# BABYBEAR.net
KiCad netlist of a schematic drawn in EAGLE
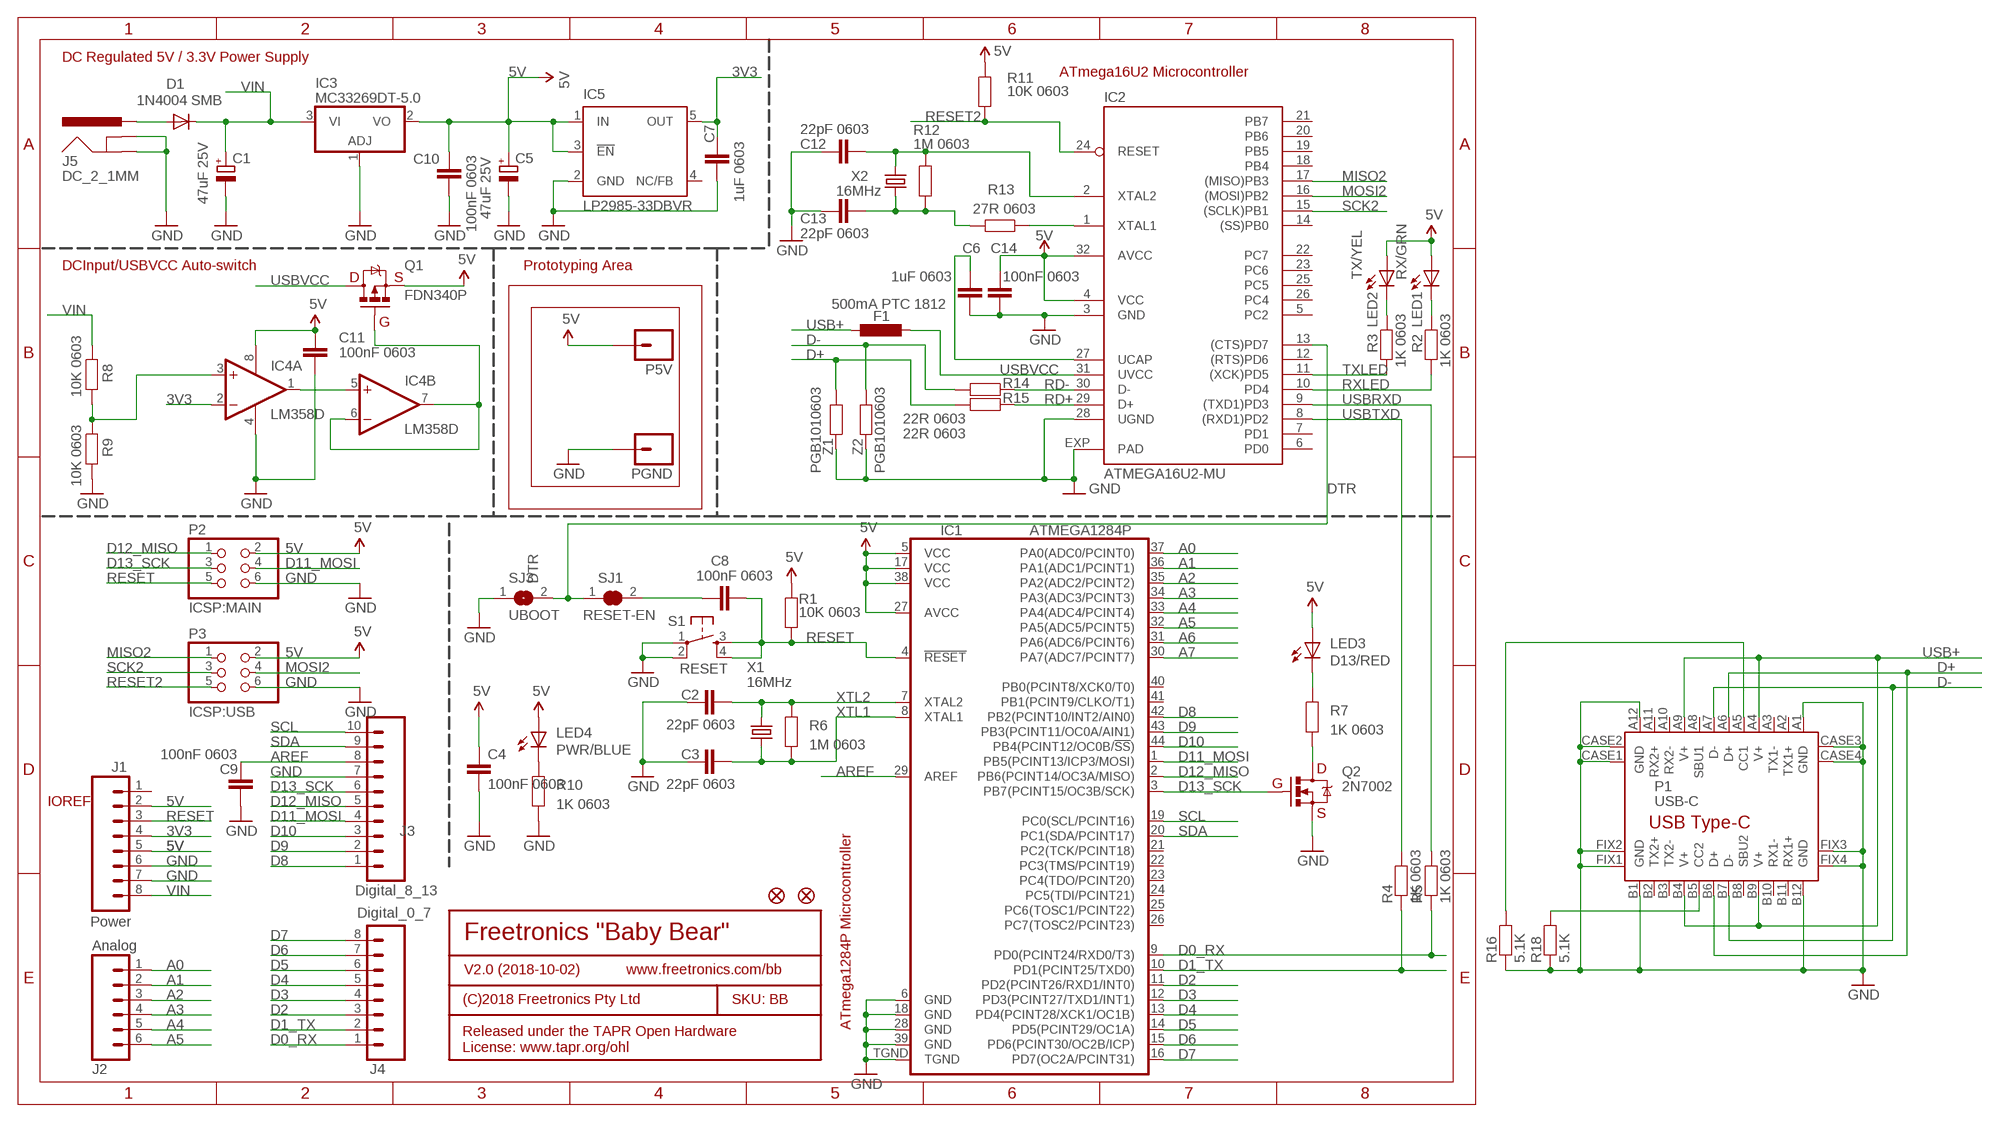
[diagram p0: schematic, sheet 1]

(export (version "E")
  (design (tool "Eeschema 10.0.6"))
  (components
    (comp (ref "C1")
      (value "47uF 25V")
      (footprint "eagle-import:PANASONIC_D")
      (libsource (lib "eagle-import") (part "CPOL-EUD"))
    )
    (comp (ref "C2")
      (value "22pF 0603")
      (footprint "eagle-import:0603")
      (libsource (lib "eagle-import") (part "CAP0603"))
    )
    (comp (ref "C3")
      (value "22pF 0603")
      (footprint "eagle-import:0603")
      (libsource (lib "eagle-import") (part "CAP0603"))
    )
    (comp (ref "C4")
      (value "100nF 0603")
      (footprint "eagle-import:0603")
      (libsource (lib "eagle-import") (part "CAP0603"))
    )
    (comp (ref "C5")
      (value "47uF 25V")
      (footprint "eagle-import:PANASONIC_D")
      (libsource (lib "eagle-import") (part "CPOL-EUD"))
    )
    (comp (ref "C6")
      (value "1uF 0603")
      (footprint "eagle-import:0603")
      (libsource (lib "eagle-import") (part "CAP0603"))
    )
    (comp (ref "C7")
      (value "1uF 0603")
      (footprint "eagle-import:0603")
      (libsource (lib "eagle-import") (part "CAP0603"))
    )
    (comp (ref "C8")
      (value "100nF 0603")
      (footprint "eagle-import:0603")
      (libsource (lib "eagle-import") (part "CAP0603"))
    )
    (comp (ref "C9")
      (value "100nF 0603")
      (footprint "eagle-import:0603")
      (libsource (lib "eagle-import") (part "CAP0603"))
    )
    (comp (ref "C10")
      (value "100nF 0603")
      (footprint "eagle-import:0603")
      (libsource (lib "eagle-import") (part "CAP0603"))
    )
    (comp (ref "C11")
      (value "100nF 0603")
      (footprint "eagle-import:0603")
      (libsource (lib "eagle-import") (part "CAP0603"))
    )
    (comp (ref "C12")
      (value "22pF 0603")
      (footprint "eagle-import:0603")
      (libsource (lib "eagle-import") (part "CAP0603"))
    )
    (comp (ref "C13")
      (value "22pF 0603")
      (footprint "eagle-import:0603")
      (libsource (lib "eagle-import") (part "CAP0603"))
    )
    (comp (ref "C14")
      (value "100nF 0603")
      (footprint "eagle-import:0603")
      (libsource (lib "eagle-import") (part "CAP0603"))
    )
    (comp (ref "D1")
      (value "1N4004 SMB")
      (footprint "eagle-import:SMB-DIODE")
      (libsource (lib "eagle-import") (part "DIODESMB"))
    )
    (comp (ref "F1")
      (value "500mA PTC 1812")
      (footprint "eagle-import:L1812")
      (libsource (lib "eagle-import") (part "L-EUL1812"))
    )
    (comp (ref "IC1")
      (value "ATMEGA1284P")
      (footprint "eagle-import:QFN-44M1")
      (libsource (lib "eagle-import") (part "ATMEGA1284P"))
    )
    (comp (ref "IC2")
      (value "ATMEGA16U2-MU")
      (footprint "eagle-import:ATMEL_QFN32")
      (libsource (lib "eagle-import") (part "ATMEL_ATMEGA8U2-MUQFN"))
    )
    (comp (ref "IC3")
      (value "MC33269DT-5.0")
      (footprint "eagle-import:DPACK")
      (libsource (lib "eagle-import") (part "MC33269?D-5.0"))
    )
    (comp (ref "IC4")
      (value "LM358D")
      (footprint "eagle-import:SO08")
      (libsource (lib "eagle-import") (part "LM358D"))
    )
    (comp (ref "IC5")
      (value "LP2985-33DBVR")
      (footprint "eagle-import:TEXAS_SOT23-DBV")
      (libsource (lib "eagle-import") (part "TEXAS_TPS77033"))
    )
    (comp (ref "J1")
      (value "Power")
      (footprint "eagle-import:1X08")
      (libsource (lib "eagle-import") (part "M08"))
    )
    (comp (ref "J2")
      (value "Analog")
      (footprint "eagle-import:1X06")
      (libsource (lib "eagle-import") (part "M06SIP"))
    )
    (comp (ref "J3")
      (value "Digital_8_13")
      (footprint "eagle-import:1X10")
      (libsource (lib "eagle-import") (part "M100.1"))
    )
    (comp (ref "J4")
      (value "Digital_0_7")
      (footprint "eagle-import:1X08")
      (libsource (lib "eagle-import") (part "M08"))
    )
    (comp (ref "J5")
      (value "DC_2_1MM")
      (footprint "eagle-import:POWER_JACK_PTH_SLOTS")
      (libsource (lib "eagle-import") (part "POWER_JACKPTH_SLOTS"))
    )
    (comp (ref "LED1")
      (value "RX/GRN")
      (footprint "eagle-import:LED-0603")
      (libsource (lib "eagle-import") (part "LED0603"))
    )
    (comp (ref "LED2")
      (value "TX/YEL")
      (footprint "eagle-import:LED-0603")
      (libsource (lib "eagle-import") (part "LED0603"))
    )
    (comp (ref "LED3")
      (value "D13/RED")
      (footprint "eagle-import:LED-0603")
      (libsource (lib "eagle-import") (part "LED0603"))
    )
    (comp (ref "LED4")
      (value "PWR/BLUE")
      (footprint "eagle-import:LED-0603")
      (libsource (lib "eagle-import") (part "LED0603"))
    )
    (comp (ref "P1")
      (value "USB-C")
      (footprint "eagle-import:USB-C-U52A")
      (libsource (lib "eagle-import") (part "USB-C"))
    )
    (comp (ref "P2")
      (value "ICSP:MAIN")
      (footprint "eagle-import:2X03")
      (libsource (lib "eagle-import") (part "PINHD-2X3"))
    )
    (comp (ref "P3")
      (value "ICSP:USB")
      (footprint "eagle-import:2X03")
      (libsource (lib "eagle-import") (part "PINHD-2X3"))
    )
    (comp (ref "P5V")
      (value "M01SMD")
      (footprint "eagle-import:LUXEON-PAD")
      (libsource (lib "eagle-import") (part "M01SMD"))
    )
    (comp (ref "PGND")
      (value "M01SMD")
      (footprint "eagle-import:LUXEON-PAD")
      (libsource (lib "eagle-import") (part "M01SMD"))
    )
    (comp (ref "Q1")
      (value "FDN340P")
      (footprint "eagle-import:SOT23")
      (libsource (lib "eagle-import") (part "MOSFET-PCHANNEL"))
    )
    (comp (ref "Q2")
      (value "2N7002")
      (footprint "eagle-import:SOT23-3")
      (libsource (lib "eagle-import") (part "MOSFET-NCHANNELSMD"))
    )
    (comp (ref "R1")
      (value "10K 0603")
      (footprint "eagle-import:0603")
      (libsource (lib "eagle-import") (part "RESISTOR0603"))
    )
    (comp (ref "R2")
      (value "1K 0603")
      (footprint "eagle-import:0603")
      (libsource (lib "eagle-import") (part "RESISTOR0603"))
    )
    (comp (ref "R3")
      (value "1K 0603")
      (footprint "eagle-import:0603")
      (libsource (lib "eagle-import") (part "RESISTOR0603"))
    )
    (comp (ref "R4")
      (value "1K 0603")
      (footprint "eagle-import:0603")
      (libsource (lib "eagle-import") (part "RESISTOR0603"))
    )
    (comp (ref "R5")
      (value "1K 0603")
      (footprint "eagle-import:0603")
      (libsource (lib "eagle-import") (part "RESISTOR0603"))
    )
    (comp (ref "R6")
      (value "1M 0603")
      (footprint "eagle-import:0603")
      (libsource (lib "eagle-import") (part "RESISTOR0603"))
    )
    (comp (ref "R7")
      (value "1K 0603")
      (footprint "eagle-import:0603")
      (libsource (lib "eagle-import") (part "RESISTOR0603"))
    )
    (comp (ref "R8")
      (value "10K 0603")
      (footprint "eagle-import:0603")
      (libsource (lib "eagle-import") (part "RESISTOR0603"))
    )
    (comp (ref "R9")
      (value "10K 0603")
      (footprint "eagle-import:0603")
      (libsource (lib "eagle-import") (part "RESISTOR0603"))
    )
    (comp (ref "R10")
      (value "1K 0603")
      (footprint "eagle-import:0603")
      (libsource (lib "eagle-import") (part "RESISTOR0603"))
    )
    (comp (ref "R11")
      (value "10K 0603")
      (footprint "eagle-import:0603")
      (libsource (lib "eagle-import") (part "RESISTOR0603"))
    )
    (comp (ref "R12")
      (value "1M 0603")
      (footprint "eagle-import:0603")
      (libsource (lib "eagle-import") (part "RESISTOR0603"))
    )
    (comp (ref "R13")
      (value "27R 0603")
      (footprint "eagle-import:0603")
      (libsource (lib "eagle-import") (part "RESISTOR0603"))
    )
    (comp (ref "R14")
      (value "22R 0603")
      (footprint "eagle-import:0603")
      (libsource (lib "eagle-import") (part "RESISTOR0603"))
    )
    (comp (ref "R15")
      (value "22R 0603")
      (footprint "eagle-import:0603")
      (libsource (lib "eagle-import") (part "RESISTOR0603"))
    )
    (comp (ref "R16")
      (value "5.1K")
      (footprint "eagle-import:0603")
      (libsource (lib "eagle-import") (part "freetronics-original_RESISTOR0603"))
    )
    (comp (ref "R18")
      (value "5.1K")
      (footprint "eagle-import:0603")
      (libsource (lib "eagle-import") (part "freetronics-original_RESISTOR0603"))
    )
    (comp (ref "S1")
      (value "RESET")
      (footprint "eagle-import:TACTILE_SWITCH_SMD")
      (libsource (lib "eagle-import") (part "TAC_SWITCHSMD"))
    )
    (comp (ref "SJ1")
      (value "RESET-EN")
      (footprint "eagle-import:SJC")
      (libsource (lib "eagle-import") (part "SJCN"))
    )
    (comp (ref "SJ3")
      (value "UBOOT")
      (footprint "eagle-import:SJ")
      (libsource (lib "eagle-import") (part "SJ"))
    )
    (comp (ref "U$5")
      (value "FIDUCIAL1X2.5")
      (footprint "eagle-import:FIDUCIAL-1X2.5")
      (libsource (lib "eagle-import") (part "FIDUCIAL1X2.5"))
    )
    (comp (ref "U$14")
      (value "FIDUCIAL1X2.5")
      (footprint "eagle-import:FIDUCIAL-1X2.5")
      (libsource (lib "eagle-import") (part "FIDUCIAL1X2.5"))
    )
    (comp (ref "X1")
      (value "16MHz")
      (footprint "eagle-import:HC49U-V")
      (libsource (lib "eagle-import") (part "CRYSTALHC49UV"))
    )
    (comp (ref "X2")
      (value "16MHz")
      (footprint "eagle-import:HC49U-V")
      (libsource (lib "eagle-import") (part "CRYSTALHC49UV"))
    )
    (comp (ref "Z1")
      (value "PGB1010603")
      (footprint "eagle-import:0603")
      (libsource (lib "eagle-import") (part "RESISTOR0603"))
    )
    (comp (ref "Z2")
      (value "PGB1010603")
      (footprint "eagle-import:0603")
      (libsource (lib "eagle-import") (part "RESISTOR0603"))
    )
  )
  (nets
    (net (code "1") (name "/3V3") (class "Default")
      (node (ref "C7") (pin "2") (pinfunction "2_2") (pintype "passive"))
      (node (ref "IC4") (pin "2") (pinfunction "-IN_2") (pintype "input"))
      (node (ref "IC5") (pin "5") (pinfunction "OUT_5") (pintype "passive"))
      (node (ref "J1") (pin "4") (pinfunction "4_4") (pintype "passive"))
    )
    (net (code "2") (name "/A0") (class "Default")
      (node (ref "IC1") (pin "37") (pinfunction "PA0(ADC0/PCINT0)_37") (pintype "bidirectional"))
      (node (ref "J2") (pin "1") (pinfunction "1_1") (pintype "passive"))
    )
    (net (code "3") (name "/A1") (class "Default")
      (node (ref "IC1") (pin "36") (pinfunction "PA1(ADC1/PCINT1)_36") (pintype "bidirectional"))
      (node (ref "J2") (pin "2") (pinfunction "2_2") (pintype "passive"))
    )
    (net (code "4") (name "/A2") (class "Default")
      (node (ref "IC1") (pin "35") (pinfunction "PA2(ADC2/PCINT2)_35") (pintype "bidirectional"))
      (node (ref "J2") (pin "3") (pinfunction "3_3") (pintype "passive"))
    )
    (net (code "5") (name "/A3") (class "Default")
      (node (ref "IC1") (pin "34") (pinfunction "PA3(ADC3/PCINT3)_34") (pintype "bidirectional"))
      (node (ref "J2") (pin "4") (pinfunction "4_4") (pintype "passive"))
    )
    (net (code "6") (name "/A4") (class "Default")
      (node (ref "IC1") (pin "33") (pinfunction "PA4(ADC4/PCINT4)_33") (pintype "bidirectional"))
      (node (ref "J2") (pin "5") (pinfunction "5_5") (pintype "passive"))
    )
    (net (code "7") (name "/A5") (class "Default")
      (node (ref "IC1") (pin "32") (pinfunction "PA5(ADC5/PCINT5)_32") (pintype "bidirectional"))
      (node (ref "J2") (pin "6") (pinfunction "6_6") (pintype "passive"))
    )
    (net (code "8") (name "/A6") (class "Default")
      (node (ref "IC1") (pin "31") (pinfunction "PA6(ADC6/PCINT6)_31") (pintype "bidirectional"))
    )
    (net (code "9") (name "/A7") (class "Default")
      (node (ref "IC1") (pin "30") (pinfunction "PA7(ADC7/PCINT7)_30") (pintype "bidirectional"))
    )
    (net (code "10") (name "/AREF") (class "Default")
      (node (ref "C9") (pin "1") (pinfunction "1_1") (pintype "passive"))
      (node (ref "IC1") (pin "29") (pinfunction "AREF_29") (pintype "bidirectional"))
      (node (ref "J3") (pin "8") (pinfunction "8_8") (pintype "passive"))
    )
    (net (code "11") (name "/D+") (class "Default")
      (node (ref "P1") (pin "A6") (pinfunction "D+_A6") (pintype "bidirectional"))
      (node (ref "P1") (pin "B6") (pinfunction "D+_B6") (pintype "bidirectional"))
      (node (ref "R15") (pin "2") (pinfunction "2_2") (pintype "passive"))
      (node (ref "Z1") (pin "1") (pinfunction "1_1") (pintype "passive"))
    )
    (net (code "12") (name "/D-") (class "Default")
      (node (ref "P1") (pin "A7") (pinfunction "D-_A7") (pintype "bidirectional"))
      (node (ref "P1") (pin "B7") (pinfunction "D-_B7") (pintype "bidirectional"))
      (node (ref "R14") (pin "2") (pinfunction "2_2") (pintype "passive"))
      (node (ref "Z2") (pin "1") (pinfunction "1_1") (pintype "passive"))
    )
    (net (code "13") (name "/D0_RX") (class "Default")
      (node (ref "IC1") (pin "9") (pinfunction "PD0(PCINT24/RXD0/T3)_9") (pintype "bidirectional"))
      (node (ref "J4") (pin "1") (pinfunction "1_1") (pintype "passive"))
      (node (ref "R5") (pin "1") (pinfunction "1_1") (pintype "passive"))
    )
    (net (code "14") (name "/D1_TX") (class "Default")
      (node (ref "IC1") (pin "10") (pinfunction "PD1(PCINT25/TXD0)_10") (pintype "bidirectional"))
      (node (ref "J4") (pin "2") (pinfunction "2_2") (pintype "passive"))
      (node (ref "R4") (pin "1") (pinfunction "1_1") (pintype "passive"))
    )
    (net (code "15") (name "/D2") (class "Default")
      (node (ref "IC1") (pin "11") (pinfunction "PD2(PCINT26/RXD1/INT0)_11") (pintype "bidirectional"))
      (node (ref "J4") (pin "3") (pinfunction "3_3") (pintype "passive"))
    )
    (net (code "16") (name "/D3") (class "Default")
      (node (ref "IC1") (pin "12") (pinfunction "PD3(PCINT27/TXD1/INT1)_12") (pintype "bidirectional"))
      (node (ref "J4") (pin "4") (pinfunction "4_4") (pintype "passive"))
    )
    (net (code "17") (name "/D4") (class "Default")
      (node (ref "IC1") (pin "13") (pinfunction "PD4(PCINT28/XCK1/OC1B)_13") (pintype "bidirectional"))
      (node (ref "J4") (pin "5") (pinfunction "5_5") (pintype "passive"))
    )
    (net (code "18") (name "/D5") (class "Default")
      (node (ref "IC1") (pin "14") (pinfunction "PD5(PCINT29/OC1A)_14") (pintype "bidirectional"))
      (node (ref "J4") (pin "6") (pinfunction "6_6") (pintype "passive"))
    )
    (net (code "19") (name "/D6") (class "Default")
      (node (ref "IC1") (pin "15") (pinfunction "PD6(PCINT30/OC2B/ICP)_15") (pintype "bidirectional"))
      (node (ref "J4") (pin "7") (pinfunction "7_7") (pintype "passive"))
    )
    (net (code "20") (name "/D7") (class "Default")
      (node (ref "IC1") (pin "16") (pinfunction "PD7(OC2A/PCINT31)_16") (pintype "bidirectional"))
      (node (ref "J4") (pin "8") (pinfunction "8_8") (pintype "passive"))
    )
    (net (code "21") (name "/D8") (class "Default")
      (node (ref "IC1") (pin "42") (pinfunction "PB2(PCINT10/INT2/AIN0)_42") (pintype "bidirectional"))
      (node (ref "J3") (pin "1") (pinfunction "1_1") (pintype "passive"))
    )
    (net (code "22") (name "/D9") (class "Default")
      (node (ref "IC1") (pin "43") (pinfunction "PB3(PCINT11/OC0A/AIN1)_43") (pintype "bidirectional"))
      (node (ref "J3") (pin "2") (pinfunction "2_2") (pintype "passive"))
    )
    (net (code "23") (name "/D10") (class "Default")
      (node (ref "IC1") (pin "44") (pinfunction "PB4(PCINT12/OC0B/~{SS})_44") (pintype "bidirectional"))
      (node (ref "J3") (pin "3") (pinfunction "3_3") (pintype "passive"))
    )
    (net (code "24") (name "/D11_MOSI") (class "Default")
      (node (ref "IC1") (pin "1") (pinfunction "PB5(PCINT13/ICP3/MOSI)_1") (pintype "bidirectional"))
      (node (ref "J3") (pin "4") (pinfunction "4_4") (pintype "passive"))
      (node (ref "P2") (pin "4") (pinfunction "4_4") (pintype "passive"))
    )
    (net (code "25") (name "/D12_MISO") (class "Default")
      (node (ref "IC1") (pin "2") (pinfunction "PB6(PCINT14/OC3A/MISO)_2") (pintype "bidirectional"))
      (node (ref "J3") (pin "5") (pinfunction "5_5") (pintype "passive"))
      (node (ref "P2") (pin "1") (pinfunction "1_1") (pintype "passive"))
    )
    (net (code "26") (name "/D13_SCK") (class "Default")
      (node (ref "IC1") (pin "3") (pinfunction "PB7(PCINT15/OC3B/SCK)_3") (pintype "bidirectional"))
      (node (ref "J3") (pin "6") (pinfunction "6_6") (pintype "passive"))
      (node (ref "P2") (pin "3") (pinfunction "3_3") (pintype "passive"))
      (node (ref "Q2") (pin "1") (pinfunction "G_1") (pintype "passive"))
    )
    (net (code "27") (name "/DTR") (class "Default")
      (node (ref "IC2") (pin "13") (pinfunction "(CTS)PD7_13") (pintype "bidirectional"))
      (node (ref "SJ1") (pin "1") (pinfunction "1_1") (pintype "passive"))
      (node (ref "SJ3") (pin "2") (pinfunction "2_2") (pintype "passive"))
    )
    (net (code "28") (name "/MISO2") (class "Default")
      (node (ref "IC2") (pin "17") (pinfunction "(MISO)PB3_17") (pintype "bidirectional"))
      (node (ref "P3") (pin "1") (pinfunction "1_1") (pintype "passive"))
    )
    (net (code "29") (name "/MOSI2") (class "Default")
      (node (ref "IC2") (pin "16") (pinfunction "(MOSI)PB2_16") (pintype "bidirectional"))
      (node (ref "P3") (pin "4") (pinfunction "4_4") (pintype "passive"))
    )
    (net (code "30") (name "/RD+") (class "Default")
      (node (ref "IC2") (pin "29") (pinfunction "D+_29") (pintype "bidirectional"))
      (node (ref "R15") (pin "1") (pinfunction "1_1") (pintype "passive"))
    )
    (net (code "31") (name "/RD-") (class "Default")
      (node (ref "IC2") (pin "30") (pinfunction "D-_30") (pintype "bidirectional"))
      (node (ref "R14") (pin "1") (pinfunction "1_1") (pintype "passive"))
    )
    (net (code "32") (name "/RESET") (class "Default")
      (node (ref "C8") (pin "2") (pinfunction "2_2") (pintype "passive"))
      (node (ref "IC1") (pin "4") (pinfunction "~{RESET}_4") (pintype "bidirectional"))
      (node (ref "J1") (pin "3") (pinfunction "3_3") (pintype "passive"))
      (node (ref "P2") (pin "5") (pinfunction "5_5") (pintype "passive"))
      (node (ref "R1") (pin "1") (pinfunction "1_1") (pintype "passive"))
      (node (ref "S1") (pin "3") (pinfunction "3_3") (pintype "passive"))
      (node (ref "S1") (pin "4") (pinfunction "4_4") (pintype "passive"))
    )
    (net (code "33") (name "/RESET2") (class "Default")
      (node (ref "IC2") (pin "24") (pinfunction "RESET_24") (pintype "input"))
      (node (ref "P3") (pin "5") (pinfunction "5_5") (pintype "passive"))
      (node (ref "R11") (pin "1") (pinfunction "1_1") (pintype "passive"))
    )
    (net (code "34") (name "/RXLED") (class "Default")
      (node (ref "IC2") (pin "10") (pinfunction "PD4_10") (pintype "bidirectional"))
      (node (ref "R2") (pin "1") (pinfunction "1_1") (pintype "passive"))
    )
    (net (code "35") (name "/SCK2") (class "Default")
      (node (ref "IC2") (pin "15") (pinfunction "(SCLK)PB1_15") (pintype "bidirectional"))
      (node (ref "P3") (pin "3") (pinfunction "3_3") (pintype "passive"))
    )
    (net (code "36") (name "/SCL") (class "Default")
      (node (ref "IC1") (pin "19") (pinfunction "PC0(SCL/PCINT16)_19") (pintype "bidirectional"))
      (node (ref "J3") (pin "10") (pinfunction "10_10") (pintype "passive"))
    )
    (net (code "37") (name "/SDA") (class "Default")
      (node (ref "IC1") (pin "20") (pinfunction "PC1(SDA/PCINT17)_20") (pintype "bidirectional"))
      (node (ref "J3") (pin "9") (pinfunction "9_9") (pintype "passive"))
    )
    (net (code "38") (name "/TXLED") (class "Default")
      (node (ref "IC2") (pin "11") (pinfunction "(XCK)PD5_11") (pintype "bidirectional"))
      (node (ref "R3") (pin "1") (pinfunction "1_1") (pintype "passive"))
    )
    (net (code "39") (name "/USB+") (class "Default")
      (node (ref "F1") (pin "1") (pinfunction "1_1") (pintype "passive"))
      (node (ref "P1") (pin "A4") (pinfunction "V+_A4") (pintype "power_in"))
      (node (ref "P1") (pin "A9") (pinfunction "V+_A9") (pintype "power_in"))
      (node (ref "P1") (pin "B4") (pinfunction "V+_B4") (pintype "power_in"))
      (node (ref "P1") (pin "B9") (pinfunction "V+_B9") (pintype "power_in"))
    )
    (net (code "40") (name "/USBRXD") (class "Default")
      (node (ref "IC2") (pin "9") (pinfunction "(TXD1)PD3_9") (pintype "bidirectional"))
      (node (ref "R5") (pin "2") (pinfunction "2_2") (pintype "passive"))
    )
    (net (code "41") (name "/USBTXD") (class "Default")
      (node (ref "IC2") (pin "8") (pinfunction "(RXD1)PD2_8") (pintype "bidirectional"))
      (node (ref "R4") (pin "2") (pinfunction "2_2") (pintype "passive"))
    )
    (net (code "42") (name "/USBVCC") (class "Default")
      (node (ref "F1") (pin "2") (pinfunction "2_2") (pintype "passive"))
      (node (ref "IC2") (pin "31") (pinfunction "UVCC_31") (pintype "power_in"))
      (node (ref "Q1") (pin "3") (pinfunction "D_3") (pintype "passive"))
    )
    (net (code "43") (name "/VIN") (class "Default")
      (node (ref "C1") (pin "+") (pinfunction "+_+") (pintype "passive"))
      (node (ref "D1") (pin "C") (pinfunction "C_C") (pintype "passive"))
      (node (ref "IC3") (pin "3") (pinfunction "VI_3") (pintype "input"))
      (node (ref "J1") (pin "8") (pinfunction "8_8") (pintype "passive"))
      (node (ref "R8") (pin "2") (pinfunction "2_2") (pintype "passive"))
    )
    (net (code "44") (name "/XTL1") (class "Default")
      (node (ref "C3") (pin "2") (pinfunction "2_2") (pintype "passive"))
      (node (ref "IC1") (pin "8") (pinfunction "XTAL1_8") (pintype "bidirectional"))
      (node (ref "R6") (pin "1") (pinfunction "1_1") (pintype "passive"))
      (node (ref "X1") (pin "1") (pinfunction "1_1") (pintype "passive"))
    )
    (net (code "45") (name "/XTL2") (class "Default")
      (node (ref "C2") (pin "2") (pinfunction "2_2") (pintype "passive"))
      (node (ref "IC1") (pin "7") (pinfunction "XTAL2_7") (pintype "bidirectional"))
      (node (ref "R6") (pin "2") (pinfunction "2_2") (pintype "passive"))
      (node (ref "X1") (pin "2") (pinfunction "2_2") (pintype "passive"))
    )
    (net (code "46") (name "5V") (class "Default")
      (node (ref "C10") (pin "1") (pinfunction "1_1") (pintype "passive"))
      (node (ref "C11") (pin "1") (pinfunction "1_1") (pintype "passive"))
      (node (ref "C14") (pin "1") (pinfunction "1_1") (pintype "passive"))
      (node (ref "C4") (pin "1") (pinfunction "1_1") (pintype "passive"))
      (node (ref "C5") (pin "+") (pinfunction "+_+") (pintype "passive"))
      (node (ref "IC1") (pin "17") (pinfunction "VCC_17") (pintype "bidirectional"))
      (node (ref "IC1") (pin "27") (pinfunction "AVCC_27") (pintype "bidirectional"))
      (node (ref "IC1") (pin "38") (pinfunction "VCC_38") (pintype "bidirectional"))
      (node (ref "IC1") (pin "5") (pinfunction "VCC_5") (pintype "bidirectional"))
      (node (ref "IC2") (pin "32") (pinfunction "AVCC_32") (pintype "power_in"))
      (node (ref "IC2") (pin "4") (pinfunction "VCC_4") (pintype "power_in"))
      (node (ref "IC3") (pin "2") (pinfunction "VO_2") (pintype "passive"))
      (node (ref "IC4") (pin "8") (pinfunction "V+_8") (pintype "power_in"))
      (node (ref "IC5") (pin "1") (pinfunction "IN_1") (pintype "input"))
      (node (ref "IC5") (pin "3") (pinfunction "~{EN}_3") (pintype "input"))
      (node (ref "J1") (pin "2") (pinfunction "2_2") (pintype "passive"))
      (node (ref "J1") (pin "5") (pinfunction "5_5") (pintype "passive"))
      (node (ref "LED1") (pin "A") (pinfunction "A_A") (pintype "passive"))
      (node (ref "LED2") (pin "A") (pinfunction "A_A") (pintype "passive"))
      (node (ref "LED3") (pin "A") (pinfunction "A_A") (pintype "passive"))
      (node (ref "LED4") (pin "A") (pinfunction "A_A") (pintype "passive"))
      (node (ref "P2") (pin "2") (pinfunction "2_2") (pintype "passive"))
      (node (ref "P3") (pin "2") (pinfunction "2_2") (pintype "passive"))
      (node (ref "P5V") (pin "P$1") (pinfunction "1_P$1") (pintype "passive"))
      (node (ref "Q1") (pin "2") (pinfunction "S_2") (pintype "passive"))
      (node (ref "R1") (pin "2") (pinfunction "2_2") (pintype "passive"))
      (node (ref "R11") (pin "2") (pinfunction "2_2") (pintype "passive"))
    )
    (net (code "47") (name "GND") (class "Default")
      (node (ref "C1") (pin "-") (pinfunction "-_-") (pintype "passive"))
      (node (ref "C10") (pin "2") (pinfunction "2_2") (pintype "passive"))
      (node (ref "C11") (pin "2") (pinfunction "2_2") (pintype "passive"))
      (node (ref "C12") (pin "1") (pinfunction "1_1") (pintype "passive"))
      (node (ref "C13") (pin "1") (pinfunction "1_1") (pintype "passive"))
      (node (ref "C14") (pin "2") (pinfunction "2_2") (pintype "passive"))
      (node (ref "C2") (pin "1") (pinfunction "1_1") (pintype "passive"))
      (node (ref "C3") (pin "1") (pinfunction "1_1") (pintype "passive"))
      (node (ref "C4") (pin "2") (pinfunction "2_2") (pintype "passive"))
      (node (ref "C5") (pin "-") (pinfunction "-_-") (pintype "passive"))
      (node (ref "C6") (pin "2") (pinfunction "2_2") (pintype "passive"))
      (node (ref "C7") (pin "1") (pinfunction "1_1") (pintype "passive"))
      (node (ref "C9") (pin "2") (pinfunction "2_2") (pintype "passive"))
      (node (ref "IC1") (pin "18") (pinfunction "GND_18") (pintype "bidirectional"))
      (node (ref "IC1") (pin "28") (pinfunction "GND_28") (pintype "bidirectional"))
      (node (ref "IC1") (pin "39") (pinfunction "GND_39") (pintype "bidirectional"))
      (node (ref "IC1") (pin "6") (pinfunction "GND_6") (pintype "bidirectional"))
      (node (ref "IC1") (pin "TGND") (pinfunction "TGND_TGND") (pintype "bidirectional"))
      (node (ref "IC2") (pin "28") (pinfunction "UGND_28") (pintype "power_in"))
      (node (ref "IC2") (pin "3") (pinfunction "GND_3") (pintype "power_in"))
      (node (ref "IC2") (pin "EXP") (pinfunction "PAD_EXP") (pintype "power_in"))
      (node (ref "IC3") (pin "1") (pinfunction "ADJ_1") (pintype "input"))
      (node (ref "IC4") (pin "4") (pinfunction "V-_4") (pintype "power_in"))
      (node (ref "IC5") (pin "2") (pinfunction "GND_2") (pintype "power_in"))
      (node (ref "J1") (pin "6") (pinfunction "6_6") (pintype "passive"))
      (node (ref "J1") (pin "7") (pinfunction "7_7") (pintype "passive"))
      (node (ref "J3") (pin "7") (pinfunction "7_7") (pintype "passive"))
      (node (ref "J5") (pin "GND") (pinfunction "GND_GND") (pintype "bidirectional"))
      (node (ref "J5") (pin "GNDBREAK") (pinfunction "GNDBREAK_GNDBREAK") (pintype "bidirectional"))
      (node (ref "P1") (pin "A1") (pinfunction "GND_A1") (pintype "power_in"))
      (node (ref "P1") (pin "A12") (pinfunction "GND_A12") (pintype "power_in"))
      (node (ref "P1") (pin "B1") (pinfunction "GND_B1") (pintype "power_in"))
      (node (ref "P1") (pin "B12") (pinfunction "GND_B12") (pintype "power_in"))
      (node (ref "P1") (pin "CASE1") (pinfunction "GND_CASE1") (pintype "power_in"))
      (node (ref "P1") (pin "CASE2") (pinfunction "GND_CASE2") (pintype "power_in"))
      (node (ref "P1") (pin "CASE3") (pinfunction "GND_CASE3") (pintype "power_in"))
      (node (ref "P1") (pin "CASE4") (pinfunction "GND_CASE4") (pintype "power_in"))
      (node (ref "P1") (pin "FIX1") (pinfunction "GND_FIX1") (pintype "power_in"))
      (node (ref "P1") (pin "FIX2") (pinfunction "GND_FIX2") (pintype "power_in"))
      (node (ref "P1") (pin "FIX3") (pinfunction "GND_FIX3") (pintype "power_in"))
      (node (ref "P1") (pin "FIX4") (pinfunction "GND_FIX4") (pintype "power_in"))
      (node (ref "P2") (pin "6") (pinfunction "6_6") (pintype "passive"))
      (node (ref "P3") (pin "6") (pinfunction "6_6") (pintype "passive"))
      (node (ref "PGND") (pin "P$1") (pinfunction "1_P$1") (pintype "passive"))
      (node (ref "Q2") (pin "2") (pinfunction "S_2") (pintype "passive"))
      (node (ref "R10") (pin "1") (pinfunction "1_1") (pintype "passive"))
      (node (ref "R16") (pin "1") (pinfunction "1_1") (pintype "passive"))
      (node (ref "R18") (pin "1") (pinfunction "1_1") (pintype "passive"))
      (node (ref "R9") (pin "1") (pinfunction "1_1") (pintype "passive"))
      (node (ref "S1") (pin "1") (pinfunction "1_1") (pintype "passive"))
      (node (ref "S1") (pin "2") (pinfunction "2_2") (pintype "passive"))
      (node (ref "SJ3") (pin "1") (pinfunction "1_1") (pintype "passive"))
      (node (ref "Z1") (pin "2") (pinfunction "2_2") (pintype "passive"))
      (node (ref "Z2") (pin "2") (pinfunction "2_2") (pintype "passive"))
    )
    (net (code "48") (name "Net-(C8-Pad1)") (class "Default")
      (node (ref "C8") (pin "1") (pinfunction "1_1") (pintype "passive"))
      (node (ref "SJ1") (pin "2") (pinfunction "2_2") (pintype "passive"))
    )
    (net (code "49") (name "Net-(C13-Pad2)") (class "Default")
      (node (ref "C13") (pin "2") (pinfunction "2_2") (pintype "passive"))
      (node (ref "R12") (pin "1") (pinfunction "1_1") (pintype "passive"))
      (node (ref "R13") (pin "2") (pinfunction "2_2") (pintype "passive"))
      (node (ref "X2") (pin "1") (pinfunction "1_1") (pintype "passive"))
    )
    (net (code "50") (name "Net-(D1-PadA)") (class "Default")
      (node (ref "D1") (pin "A") (pinfunction "A_A") (pintype "passive"))
      (node (ref "J5") (pin "PWR") (pinfunction "PWR_PWR") (pintype "bidirectional"))
    )
    (net (code "51") (name "Net-(IC2-UCAP)") (class "Default")
      (node (ref "C6") (pin "1") (pinfunction "1_1") (pintype "passive"))
      (node (ref "IC2") (pin "27") (pinfunction "UCAP_27") (pintype "passive"))
    )
    (net (code "52") (name "Net-(IC2-XTAL1)") (class "Default")
      (node (ref "IC2") (pin "1") (pinfunction "XTAL1_1") (pintype "bidirectional"))
      (node (ref "R13") (pin "1") (pinfunction "1_1") (pintype "passive"))
    )
    (net (code "53") (name "Net-(IC2-XTAL2)") (class "Default")
      (node (ref "C12") (pin "2") (pinfunction "2_2") (pintype "passive"))
      (node (ref "IC2") (pin "2") (pinfunction "XTAL2_2") (pintype "bidirectional"))
      (node (ref "R12") (pin "2") (pinfunction "2_2") (pintype "passive"))
      (node (ref "X2") (pin "2") (pinfunction "2_2") (pintype "passive"))
    )
    (net (code "54") (name "Net-(IC4A-+IN)") (class "Default")
      (node (ref "IC4") (pin "3") (pinfunction "+IN_3") (pintype "input"))
      (node (ref "R8") (pin "1") (pinfunction "1_1") (pintype "passive"))
      (node (ref "R9") (pin "2") (pinfunction "2_2") (pintype "passive"))
    )
    (net (code "55") (name "Net-(IC4A-OUT)") (class "Default")
      (node (ref "IC4") (pin "1") (pinfunction "OUT_1") (pintype "output"))
      (node (ref "IC4") (pin "5") (pinfunction "+IN_5") (pintype "input"))
    )
    (net (code "56") (name "Net-(IC4B--IN)") (class "Default")
      (node (ref "IC4") (pin "6") (pinfunction "-IN_6") (pintype "input"))
      (node (ref "IC4") (pin "7") (pinfunction "OUT_7") (pintype "output"))
      (node (ref "Q1") (pin "1") (pinfunction "G_1") (pintype "passive"))
    )
    (net (code "57") (name "Net-(LED1-PadC)") (class "Default")
      (node (ref "LED1") (pin "C") (pinfunction "C_C") (pintype "passive"))
      (node (ref "R2") (pin "2") (pinfunction "2_2") (pintype "passive"))
    )
    (net (code "58") (name "Net-(LED2-PadC)") (class "Default")
      (node (ref "LED2") (pin "C") (pinfunction "C_C") (pintype "passive"))
      (node (ref "R3") (pin "2") (pinfunction "2_2") (pintype "passive"))
    )
    (net (code "59") (name "Net-(LED3-PadC)") (class "Default")
      (node (ref "LED3") (pin "C") (pinfunction "C_C") (pintype "passive"))
      (node (ref "R7") (pin "2") (pinfunction "2_2") (pintype "passive"))
    )
    (net (code "60") (name "Net-(LED4-PadC)") (class "Default")
      (node (ref "LED4") (pin "C") (pinfunction "C_C") (pintype "passive"))
      (node (ref "R10") (pin "2") (pinfunction "2_2") (pintype "passive"))
    )
    (net (code "61") (name "Net-(P1-CC1)") (class "Default")
      (node (ref "P1") (pin "A5") (pinfunction "CC1_A5") (pintype "bidirectional"))
      (node (ref "R16") (pin "2") (pinfunction "2_2") (pintype "passive"))
    )
    (net (code "62") (name "Net-(P1-CC2)") (class "Default")
      (node (ref "P1") (pin "B5") (pinfunction "CC2_B5") (pintype "bidirectional"))
      (node (ref "R18") (pin "2") (pinfunction "2_2") (pintype "passive"))
    )
    (net (code "63") (name "Net-(Q2-D)") (class "Default")
      (node (ref "Q2") (pin "3") (pinfunction "D_3") (pintype "passive"))
      (node (ref "R7") (pin "1") (pinfunction "1_1") (pintype "passive"))
    )
    (net (code "64") (name "unconnected-(IC1-PB0(PCINT8{slash}XCK0{slash}T0)-Pad40)") (class "Default")
      (node (ref "IC1") (pin "40") (pinfunction "PB0(PCINT8/XCK0/T0)_40") (pintype "bidirectional"))
    )
    (net (code "65") (name "unconnected-(IC1-PB1(PCINT9{slash}CLKO{slash}T1)-Pad41)") (class "Default")
      (node (ref "IC1") (pin "41") (pinfunction "PB1(PCINT9/CLKO/T1)_41") (pintype "bidirectional"))
    )
    (net (code "66") (name "unconnected-(IC1-PC2(TCK{slash}PCINT18)-Pad21)") (class "Default")
      (node (ref "IC1") (pin "21") (pinfunction "PC2(TCK/PCINT18)_21") (pintype "bidirectional"))
    )
    (net (code "67") (name "unconnected-(IC1-PC3(TMS{slash}PCINT19)-Pad22)") (class "Default")
      (node (ref "IC1") (pin "22") (pinfunction "PC3(TMS/PCINT19)_22") (pintype "bidirectional"))
    )
    (net (code "68") (name "unconnected-(IC1-PC4(TDO{slash}PCINT20)-Pad23)") (class "Default")
      (node (ref "IC1") (pin "23") (pinfunction "PC4(TDO/PCINT20)_23") (pintype "bidirectional"))
    )
    (net (code "69") (name "unconnected-(IC1-PC5(TDI{slash}PCINT21)-Pad24)") (class "Default")
      (node (ref "IC1") (pin "24") (pinfunction "PC5(TDI/PCINT21)_24") (pintype "bidirectional"))
    )
    (net (code "70") (name "unconnected-(IC1-PC6(TOSC1{slash}PCINT22)-Pad25)") (class "Default")
      (node (ref "IC1") (pin "25") (pinfunction "PC6(TOSC1/PCINT22)_25") (pintype "bidirectional"))
    )
    (net (code "71") (name "unconnected-(IC1-PC7(TOSC2{slash}PCINT23)-Pad26)") (class "Default")
      (node (ref "IC1") (pin "26") (pinfunction "PC7(TOSC2/PCINT23)_26") (pintype "bidirectional"))
    )
    (net (code "72") (name "unconnected-(IC2-(RTS)PD6-Pad12)") (class "Default")
      (node (ref "IC2") (pin "12") (pinfunction "(RTS)PD6_12") (pintype "bidirectional"))
    )
    (net (code "73") (name "unconnected-(IC2-(SS)PB0-Pad14)") (class "Default")
      (node (ref "IC2") (pin "14") (pinfunction "(SS)PB0_14") (pintype "bidirectional"))
    )
    (net (code "74") (name "unconnected-(IC2-PB4-Pad18)") (class "Default")
      (node (ref "IC2") (pin "18") (pinfunction "PB4_18") (pintype "bidirectional"))
    )
    (net (code "75") (name "unconnected-(IC2-PB5-Pad19)") (class "Default")
      (node (ref "IC2") (pin "19") (pinfunction "PB5_19") (pintype "bidirectional"))
    )
    (net (code "76") (name "unconnected-(IC2-PB6-Pad20)") (class "Default")
      (node (ref "IC2") (pin "20") (pinfunction "PB6_20") (pintype "bidirectional"))
    )
    (net (code "77") (name "unconnected-(IC2-PB7-Pad21)") (class "Default")
      (node (ref "IC2") (pin "21") (pinfunction "PB7_21") (pintype "bidirectional"))
    )
    (net (code "78") (name "unconnected-(IC2-PC2-Pad5)") (class "Default")
      (node (ref "IC2") (pin "5") (pinfunction "PC2_5") (pintype "bidirectional"))
    )
    (net (code "79") (name "unconnected-(IC2-PC4-Pad26)") (class "Default")
      (node (ref "IC2") (pin "26") (pinfunction "PC4_26") (pintype "bidirectional"))
    )
    (net (code "80") (name "unconnected-(IC2-PC5-Pad25)") (class "Default")
      (node (ref "IC2") (pin "25") (pinfunction "PC5_25") (pintype "bidirectional"))
    )
    (net (code "81") (name "unconnected-(IC2-PC6-Pad23)") (class "Default")
      (node (ref "IC2") (pin "23") (pinfunction "PC6_23") (pintype "bidirectional"))
    )
    (net (code "82") (name "unconnected-(IC2-PC7-Pad22)") (class "Default")
      (node (ref "IC2") (pin "22") (pinfunction "PC7_22") (pintype "bidirectional"))
    )
    (net (code "83") (name "unconnected-(IC2-PD0-Pad6)") (class "Default")
      (node (ref "IC2") (pin "6") (pinfunction "PD0_6") (pintype "bidirectional"))
    )
    (net (code "84") (name "unconnected-(IC2-PD1-Pad7)") (class "Default")
      (node (ref "IC2") (pin "7") (pinfunction "PD1_7") (pintype "bidirectional"))
    )
    (net (code "85") (name "unconnected-(IC5-NC{slash}FB-Pad4)") (class "Default")
      (node (ref "IC5") (pin "4") (pinfunction "NC/FB_4") (pintype "passive"))
    )
    (net (code "86") (name "unconnected-(J1-Pad1)") (class "Default")
      (node (ref "J1") (pin "1") (pinfunction "1_1") (pintype "passive"))
    )
    (net (code "87") (name "unconnected-(P1-RX1+-PadB11)") (class "Default")
      (node (ref "P1") (pin "B11") (pinfunction "RX1+_B11") (pintype "bidirectional"))
    )
    (net (code "88") (name "unconnected-(P1-RX1--PadB10)") (class "Default")
      (node (ref "P1") (pin "B10") (pinfunction "RX1-_B10") (pintype "bidirectional"))
    )
    (net (code "89") (name "unconnected-(P1-RX2+-PadA11)") (class "Default")
      (node (ref "P1") (pin "A11") (pinfunction "RX2+_A11") (pintype "bidirectional"))
    )
    (net (code "90") (name "unconnected-(P1-RX2--PadA10)") (class "Default")
      (node (ref "P1") (pin "A10") (pinfunction "RX2-_A10") (pintype "bidirectional"))
    )
    (net (code "91") (name "unconnected-(P1-SBU1-PadA8)") (class "Default")
      (node (ref "P1") (pin "A8") (pinfunction "SBU1_A8") (pintype "bidirectional"))
    )
    (net (code "92") (name "unconnected-(P1-SBU2-PadB8)") (class "Default")
      (node (ref "P1") (pin "B8") (pinfunction "SBU2_B8") (pintype "bidirectional"))
    )
    (net (code "93") (name "unconnected-(P1-TX1+-PadA2)") (class "Default")
      (node (ref "P1") (pin "A2") (pinfunction "TX1+_A2") (pintype "bidirectional"))
    )
    (net (code "94") (name "unconnected-(P1-TX1--PadA3)") (class "Default")
      (node (ref "P1") (pin "A3") (pinfunction "TX1-_A3") (pintype "bidirectional"))
    )
    (net (code "95") (name "unconnected-(P1-TX2+-PadB2)") (class "Default")
      (node (ref "P1") (pin "B2") (pinfunction "TX2+_B2") (pintype "bidirectional"))
    )
    (net (code "96") (name "unconnected-(P1-TX2--PadB3)") (class "Default")
      (node (ref "P1") (pin "B3") (pinfunction "TX2-_B3") (pintype "bidirectional"))
    )
  )
)
